# 04-LED-YELLOW.net
KiCad netlist of a schematic drawn in Altium Designer
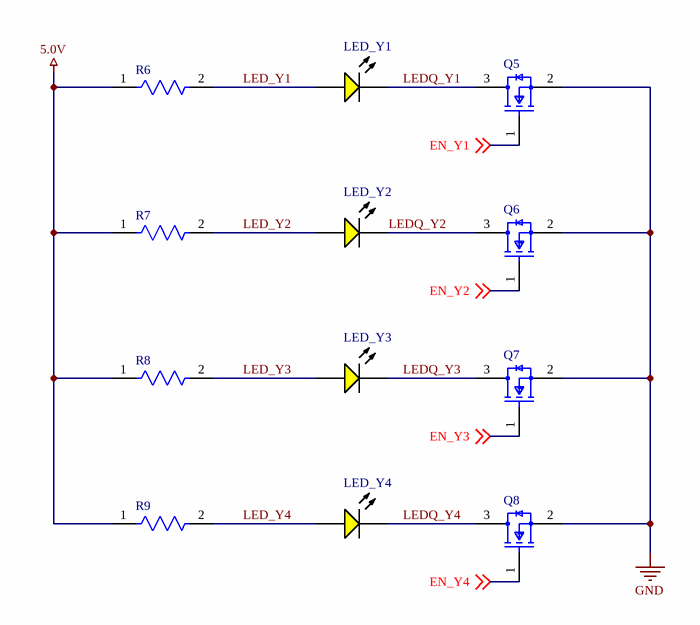
[diagram p0: 04-LED-YELLOW.SchDoc]

(export (version "E")
  (design (tool "Eeschema 10.0.6"))
  (components
    (comp (ref "LED_Y1")
      (value "SML-LX1206YC-TR")
      (footprint "LUMX-SML-LX1206YC-TR_V")
      (description "Yellow LED, Water Clear Len, 585 nm, 2.1 V, -40 to 85 degC, 2-Pin SMD, RoHS, Tape and Reel")
      (fields (field (name "MANUFACTURER") "Lumex"))
      (libsource (lib "Altium Content Vault") (part "LED-YELLOW-AK-2"))
    )
    (comp (ref "LED_Y2")
      (value "SML-LX1206YC-TR")
      (footprint "LUMX-SML-LX1206YC-TR_V")
      (description "Yellow LED, Water Clear Len, 585 nm, 2.1 V, -40 to 85 degC, 2-Pin SMD, RoHS, Tape and Reel")
      (fields (field (name "MANUFACTURER") "Lumex"))
      (libsource (lib "Altium Content Vault") (part "LED-YELLOW-AK-2"))
    )
    (comp (ref "LED_Y3")
      (value "SML-LX1206YC-TR")
      (footprint "LUMX-SML-LX1206YC-TR_V")
      (description "Yellow LED, Water Clear Len, 585 nm, 2.1 V, -40 to 85 degC, 2-Pin SMD, RoHS, Tape and Reel")
      (fields (field (name "MANUFACTURER") "Lumex"))
      (libsource (lib "Altium Content Vault") (part "LED-YELLOW-AK-2"))
    )
    (comp (ref "LED_Y4")
      (value "SML-LX1206YC-TR")
      (footprint "LUMX-SML-LX1206YC-TR_V")
      (description "Yellow LED, Water Clear Len, 585 nm, 2.1 V, -40 to 85 degC, 2-Pin SMD, RoHS, Tape and Reel")
      (fields (field (name "MANUFACTURER") "Lumex"))
      (libsource (lib "Altium Content Vault") (part "LED-YELLOW-AK-2"))
    )
    (comp (ref "Q5")
      (value "2N7002-7-F")
      (footprint "FP-SOT23-MFG")
      (description "MOSFET N-CH 60V 115MA SOT23-3")
      (fields (field (name "VOLTAGE") "60V"))
      (libsource (lib "Altium Content Vault") (part "3b9c635fedb024a5347a57b145af9cc"))
    )
    (comp (ref "Q6")
      (value "2N7002-7-F")
      (footprint "FP-SOT23-MFG")
      (description "MOSFET N-CH 60V 115MA SOT23-3")
      (fields (field (name "VOLTAGE") "60V"))
      (libsource (lib "Altium Content Vault") (part "3b9c635fedb024a5347a57b145af9cc"))
    )
    (comp (ref "Q7")
      (value "2N7002-7-F")
      (footprint "FP-SOT23-MFG")
      (description "MOSFET N-CH 60V 115MA SOT23-3")
      (fields (field (name "VOLTAGE") "60V"))
      (libsource (lib "Altium Content Vault") (part "3b9c635fedb024a5347a57b145af9cc"))
    )
    (comp (ref "Q8")
      (value "2N7002-7-F")
      (footprint "FP-SOT23-MFG")
      (description "MOSFET N-CH 60V 115MA SOT23-3")
      (fields (field (name "VOLTAGE") "60V"))
      (libsource (lib "Altium Content Vault") (part "3b9c635fedb024a5347a57b145af9cc"))
    )
    (comp (ref "R6")
      (value "CRCW1206330RFKEA")
      (footprint "FP-CRCW1206-e3-IPC_A")
      (description "RES Thick Film, 330Ω, 1%, 0.25W, 100ppm/°C, 1206")
      (fields (field (name "TOLERANCE") "1%"))
      (libsource (lib "Altium Content Vault") (part "1029c3af85768c4190bb7ad29bc67b5"))
    )
    (comp (ref "R7")
      (value "CRCW1206330RFKEA")
      (footprint "FP-CRCW1206-e3-IPC_A")
      (description "RES Thick Film, 330Ω, 1%, 0.25W, 100ppm/°C, 1206")
      (fields (field (name "TOLERANCE") "1%"))
      (libsource (lib "Altium Content Vault") (part "1029c3af85768c4190bb7ad29bc67b5"))
    )
    (comp (ref "R8")
      (value "CRCW1206330RFKEA")
      (footprint "FP-CRCW1206-e3-IPC_A")
      (description "RES Thick Film, 330Ω, 1%, 0.25W, 100ppm/°C, 1206")
      (fields (field (name "TOLERANCE") "1%"))
      (libsource (lib "Altium Content Vault") (part "1029c3af85768c4190bb7ad29bc67b5"))
    )
    (comp (ref "R9")
      (value "CRCW1206330RFKEA")
      (footprint "FP-CRCW1206-e3-IPC_A")
      (description "RES Thick Film, 330Ω, 1%, 0.25W, 100ppm/°C, 1206")
      (fields (field (name "TOLERANCE") "1%"))
      (libsource (lib "Altium Content Vault") (part "1029c3af85768c4190bb7ad29bc67b5"))
    )
  )
  (nets
    (net (code "1") (name "/LEDQ_Y1") (class "Default")
      (node (ref "LED_Y1") (pin "2") (pinfunction "K_2") (pintype "passive"))
      (node (ref "Q5") (pin "3") (pinfunction "D_3") (pintype "passive"))
    )
    (net (code "2") (name "/LEDQ_Y2") (class "Default")
      (node (ref "LED_Y2") (pin "2") (pinfunction "K_2") (pintype "passive"))
      (node (ref "Q6") (pin "3") (pinfunction "D_3") (pintype "passive"))
    )
    (net (code "3") (name "/LEDQ_Y3") (class "Default")
      (node (ref "LED_Y3") (pin "2") (pinfunction "K_2") (pintype "passive"))
      (node (ref "Q7") (pin "3") (pinfunction "D_3") (pintype "passive"))
    )
    (net (code "4") (name "/LEDQ_Y4") (class "Default")
      (node (ref "LED_Y4") (pin "2") (pinfunction "K_2") (pintype "passive"))
      (node (ref "Q8") (pin "3") (pinfunction "D_3") (pintype "passive"))
    )
    (net (code "5") (name "/LED_Y1") (class "Default")
      (node (ref "LED_Y1") (pin "1") (pinfunction "A_1") (pintype "passive"))
      (node (ref "R6") (pin "2") (pinfunction "2_2") (pintype "passive"))
    )
    (net (code "6") (name "/LED_Y2") (class "Default")
      (node (ref "LED_Y2") (pin "1") (pinfunction "A_1") (pintype "passive"))
      (node (ref "R7") (pin "2") (pinfunction "2_2") (pintype "passive"))
    )
    (net (code "7") (name "/LED_Y3") (class "Default")
      (node (ref "LED_Y3") (pin "1") (pinfunction "A_1") (pintype "passive"))
      (node (ref "R8") (pin "2") (pinfunction "2_2") (pintype "passive"))
    )
    (net (code "8") (name "/LED_Y4") (class "Default")
      (node (ref "LED_Y4") (pin "1") (pinfunction "A_1") (pintype "passive"))
      (node (ref "R9") (pin "2") (pinfunction "2_2") (pintype "passive"))
    )
    (net (code "9") (name "5.0V") (class "Default")
      (node (ref "R6") (pin "1") (pinfunction "1_1") (pintype "passive"))
      (node (ref "R7") (pin "1") (pinfunction "1_1") (pintype "passive"))
      (node (ref "R8") (pin "1") (pinfunction "1_1") (pintype "passive"))
      (node (ref "R9") (pin "1") (pinfunction "1_1") (pintype "passive"))
    )
    (net (code "10") (name "EN_Y1") (class "Default")
      (node (ref "Q5") (pin "1") (pinfunction "G_1") (pintype "passive"))
    )
    (net (code "11") (name "EN_Y2") (class "Default")
      (node (ref "Q6") (pin "1") (pinfunction "G_1") (pintype "passive"))
    )
    (net (code "12") (name "EN_Y3") (class "Default")
      (node (ref "Q7") (pin "1") (pinfunction "G_1") (pintype "passive"))
    )
    (net (code "13") (name "EN_Y4") (class "Default")
      (node (ref "Q8") (pin "1") (pinfunction "G_1") (pintype "passive"))
    )
    (net (code "14") (name "GND") (class "Default")
      (node (ref "Q5") (pin "2") (pinfunction "S_2") (pintype "passive"))
      (node (ref "Q6") (pin "2") (pinfunction "S_2") (pintype "passive"))
      (node (ref "Q7") (pin "2") (pinfunction "S_2") (pintype "passive"))
      (node (ref "Q8") (pin "2") (pinfunction "S_2") (pintype "passive"))
    )
  )
)
